# Main_Schematic.net
KiCad netlist of a schematic drawn in Altium Designer
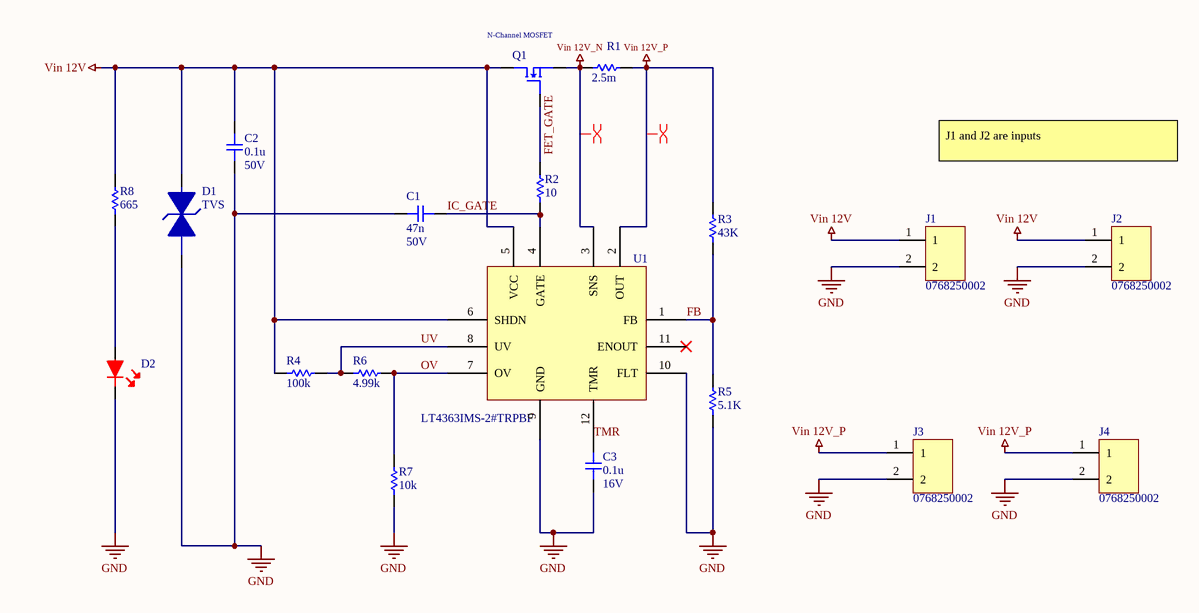
[diagram p0: Main Schematic.SchDoc]

(export (version "E")
  (design (tool "Eeschema 10.0.6"))
  (components
    (comp (ref "C1")
      (value "47n")
      (footprint "C0603")
      (description "C0603C 47nF Ceramic Multilayer Capacitor; 50 VDC; +125degC; X7R Dielec; +/-10%")
      (fields
        (field (name "MANUFACTURER") "KEMET")
        (field (name "MANUFACTURER PART NUMBER") "C0603C473K5RACTU")
        (field (name "VOLTAGE RATING (DC)") "50V")
      )
      (libsource (lib "Schlib1") (part "C0603C473K5RACTU"))
    )
    (comp (ref "C2")
      (value "0.1u")
      (footprint "C0805")
      (description "Cap Ceramic 0.1uF 50V Y5V -20% to 80% SMD 0805 85°C Paper T/R")
      (fields
        (field (name "MANUFACTURER") "KEMET")
        (field (name "MANUFACTURER PART NUMBER") "C0805C104Z5VACTU")
        (field (name "VOLTAGE RATING") "50V")
      )
      (libsource (lib "Schlib1") (part "C0805C104Z5VACTU"))
    )
    (comp (ref "C3")
      (value "0.1u")
      (footprint "C0603")
      (description "Cap Ceramic 0.1uF 16V X7R 20% SMD 0603 125°C Paper T/R")
      (fields
        (field (name "MANUFACTURER") "KEMET")
        (field (name "MANUFACTURER PART NUMBER") "C0603C104M4RACTU")
        (field (name "VOLTAGE RATING") "16V")
      )
      (libsource (lib "Schlib1") (part "C0603C104M4RACTU"))
    )
    (comp (ref "D1")
      (value "TVS")
      (footprint "TVS")
      (description "SMAJ Series 58 V 400 W SMT Uni-Directional TVS Diode - DO-214AC")
      (fields (field (name "MANUFACTURER") "Diodes") (field (name "MANUFACTURER PART NUMBER") "SMAJ58A-13-F"))
      (libsource (lib "Schlib1") (part "SMAJ58A-13-F"))
    )
    (comp (ref "D2")
      (value "R-LED")
      (footprint "D-0603")
      (description "LED Low-Power Uni-Color Red 630nm 2V 2-Pin Chip 0603(1608Metric) T/R")
      (fields
        (field (name "MANUFACTURER") "Wurth Electronics")
        (field (name "MANUFACTURER PART NUMBER") "150060RS75000")
      )
      (libsource (lib "Schlib1") (part "150060RS75000"))
    )
    (comp (ref "J1")
      (value "0768250002")
      (footprint "2X1PIN")
      (description "CONN HEADER R/A 2POS")
      (fields (field (name "MANUFACTURER") "Molex") (field (name "MANUFACTURER PART NUMBER") "76825-0002"))
      (libsource (lib "PDB_sch_lib") (part "2X1PIN"))
    )
    (comp (ref "J2")
      (value "0768250002")
      (footprint "2X1PIN")
      (description "CONN HEADER R/A 2POS")
      (fields (field (name "MANUFACTURER") "Molex") (field (name "MANUFACTURER PART NUMBER") "76825-0002"))
      (libsource (lib "PDB_sch_lib") (part "2X1PIN"))
    )
    (comp (ref "J3")
      (value "0768250002")
      (footprint "2X1PIN")
      (description "CONN HEADER R/A 2POS")
      (fields (field (name "MANUFACTURER") "Molex") (field (name "MANUFACTURER PART NUMBER") "76825-0002"))
      (libsource (lib "PDB_sch_lib") (part "2X1PIN"))
    )
    (comp (ref "J4")
      (value "0768250002")
      (footprint "2X1PIN")
      (description "CONN HEADER R/A 2POS")
      (fields (field (name "MANUFACTURER") "Molex") (field (name "MANUFACTURER PART NUMBER") "76825-0002"))
      (libsource (lib "PDB_sch_lib") (part "2X1PIN"))
    )
    (comp (ref "Q1")
      (value "N-Channel MOSFET")
      (footprint "N-MOS")
      (description "N-Channel Power MOSFET, UniFETTM, 250 V, 33 A, 94 mΩ, D2PAK")
      (fields
        (field (name "MANUFACTURER") "ON Semiconductor / Fairchild")
        (field (name "MANUFACTURER PART NUMBER") "FDB33N25TM")
      )
      (libsource (lib "Schlib1") (part "FDB33N25TM"))
    )
    (comp (ref "R1")
      (value "2.5m")
      (footprint "R3921")
      (description "Res Metal Strip 3921 0.0025 Ohm 1% 5W 50ppm/°C Pad SMD Automotive T/R")
      (fields
        (field (name "MANUFACTURER") "Vishay Dale")
        (field (name "MANUFACTURER PART NUMBER") "WSLP39212L500FEA")
      )
      (libsource (lib "Schlib1") (part "WSLP39212L500FEA"))
    )
    (comp (ref "R2")
      (value "10")
      (footprint "R0603")
      (description "KTR Series 0603 10 Ohm ±1 % 0.1 W ±100 ppm/°C Surface Mount Thick Film Resistor")
      (fields (field (name "MANUFACTURER") "Rohm") (field (name "MANUFACTURER PART NUMBER") "KTR03EZPF10R0"))
      (libsource (lib "Schlib1") (part "KTR03EZPF10R0"))
    )
    (comp (ref "R3")
      (value "43K")
      (footprint "R0603")
      (description "RNCF Precision Thin Film Chip Resistor 0603 Size 43K Ohm 0.5% 0.166 W 25 ppm/°C 2-Pin SMD T/R")
      (fields
        (field (name "MANUFACTURER") "Stackpole Electronics")
        (field (name "MANUFACTURER PART NUMBER") "RNCF0603DTE43K0")
      )
      (libsource (lib "Schlib1") (part "RNCF0603DTE43K0"))
    )
    (comp (ref "R4")
      (value "100k")
      (footprint "R0603")
      (description "Res Thick Film 0603 100K Ohm 1% 1/10W ±50ppm/°C Molded SMD Paper T/R")
      (fields
        (field (name "MANUFACTURER") "Yageo")
        (field (name "MANUFACTURER PART NUMBER") "RE0603FRE07100KL")
      )
      (libsource (lib "Schlib1") (part "RE0603FRE07100KL"))
    )
    (comp (ref "R5")
      (value "5.1K")
      (footprint "R0603")
      (description "Res Thick Film 0603 5.1K Ohm 1% 1/10W ±100ppm/°C Molded SMD Punched Carrier T/R")
      (fields
        (field (name "MANUFACTURER") "Panasonic")
        (field (name "MANUFACTURER PART NUMBER") "ERJ-3EKF5101V")
      )
      (libsource (lib "Schlib1") (part "ERJ-3EKF5101V"))
    )
    (comp (ref "R6")
      (value "4.99k")
      (footprint "R0603")
      (description "Res Thick Film 0603 4.99K Ohm 1% 1/10W ±100ppm/°C Molded SMD SMD Paper T/R")
      (fields
        (field (name "MANUFACTURER") "Stackpole Electronics")
        (field (name "MANUFACTURER PART NUMBER") "RMCF0603FT4K99")
      )
      (libsource (lib "Schlib1") (part "RMCF0603FT4K99"))
    )
    (comp (ref "R7")
      (value "10k")
      (footprint "R0603")
      (description "Res Thick Film 0603 10K Ohm 1% 1/10W ±100ppm/°C Molded SMD SMD T/R")
      (fields
        (field (name "MANUFACTURER") "Samsung")
        (field (name "MANUFACTURER PART NUMBER") "RC1608F103CS")
      )
      (libsource (lib "Schlib1") (part "RC1608F103CS"))
    )
    (comp (ref "R8")
      (value "665")
      (footprint "R0603")
      (description "Res Thick Film 0603 665 Ohm 1% 1/10W ±100ppm/°C Molded SMD Paper T/R")
      (fields
        (field (name "MANUFACTURER") "Yageo")
        (field (name "MANUFACTURER PART NUMBER") "RC0603FR-07665RL")
      )
      (libsource (lib "Schlib1") (part "RC0603FR-07665RL"))
    )
    (comp (ref "U1")
      (value "LT4363IMS-2#TRPBF")
      (footprint "TSOP65P490X110-12N")
      (description "Ms-Hot Swap/High Voltage High Voltage Surge Stopper With Current Limit. Auto-Retry After Fault")
      (fields (field (name "MANUFACTURER") "Analog Devices / Linear Technology"))
      (libsource (lib "Schlib1") (part "LT4363IMS-2#TRPBF"))
    )
  )
  (nets
    (net (code "1") (name "/FB") (class "Default")
      (node (ref "R3") (pin "1") (pinfunction "1_1") (pintype "passive"))
      (node (ref "R5") (pin "2") (pinfunction "2_2") (pintype "passive"))
      (node (ref "U1") (pin "1") (pinfunction "FB_1") (pintype "passive"))
    )
    (net (code "3") (name "/IC_GATE") (class "Default")
      (node (ref "C1") (pin "2") (pinfunction "2_2") (pintype "passive"))
      (node (ref "R2") (pin "1") (pinfunction "1_1") (pintype "passive"))
      (node (ref "U1") (pin "4") (pinfunction "GATE_4") (pintype "passive"))
    )
    (net (code "4") (name "/OV") (class "Default")
      (node (ref "R6") (pin "2") (pinfunction "2_2") (pintype "passive"))
      (node (ref "R7") (pin "2") (pinfunction "2_2") (pintype "passive"))
      (node (ref "U1") (pin "7") (pinfunction "OV_7") (pintype "passive"))
    )
    (net (code "5") (name "/TMR") (class "Default")
      (node (ref "C3") (pin "2") (pinfunction "2_2") (pintype "passive"))
      (node (ref "U1") (pin "12") (pinfunction "TMR_12") (pintype "passive"))
    )
    (net (code "6") (name "/UV") (class "Default")
      (node (ref "R4") (pin "2") (pinfunction "2_2") (pintype "passive"))
      (node (ref "R6") (pin "1") (pinfunction "1_1") (pintype "passive"))
      (node (ref "U1") (pin "8") (pinfunction "UV_8") (pintype "passive"))
    )
    (net (code "7") (name "GND") (class "Default")
      (node (ref "C1") (pin "1") (pinfunction "1_1") (pintype "passive"))
      (node (ref "C2") (pin "1") (pinfunction "1_1") (pintype "passive"))
      (node (ref "C3") (pin "1") (pinfunction "1_1") (pintype "passive"))
      (node (ref "D1") (pin "2") (pinfunction "2_2") (pintype "passive"))
      (node (ref "D2") (pin "2") (pinfunction "2_2") (pintype "passive"))
      (node (ref "J1") (pin "2") (pinfunction "2_2") (pintype "passive"))
      (node (ref "J2") (pin "2") (pinfunction "2_2") (pintype "passive"))
      (node (ref "J3") (pin "2") (pinfunction "2_2") (pintype "passive"))
      (node (ref "J4") (pin "2") (pinfunction "2_2") (pintype "passive"))
      (node (ref "R5") (pin "1") (pinfunction "1_1") (pintype "passive"))
      (node (ref "R7") (pin "1") (pinfunction "1_1") (pintype "passive"))
      (node (ref "U1") (pin "10") (pinfunction "FLT_10") (pintype "passive"))
      (node (ref "U1") (pin "9") (pinfunction "GND_9") (pintype "passive"))
    )
    (net (code "8") (name "Net-(D2-Pad1)") (class "Default")
      (node (ref "D2") (pin "1") (pinfunction "1_1") (pintype "passive"))
      (node (ref "R8") (pin "1") (pinfunction "1_1") (pintype "passive"))
    )
    (net (code "9") (name "Net-(Q1-Pad1)") (class "Default")
      (node (ref "Q1") (pin "1") (pinfunction "1_1") (pintype "passive"))
      (node (ref "R2") (pin "2") (pinfunction "2_2") (pintype "passive"))
    )
    (net (code "10") (name "Vin 12V") (class "Default")
      (node (ref "C2") (pin "2") (pinfunction "2_2") (pintype "passive"))
      (node (ref "D1") (pin "1") (pinfunction "1_1") (pintype "passive"))
      (node (ref "J1") (pin "1") (pinfunction "1_1") (pintype "passive"))
      (node (ref "J2") (pin "1") (pinfunction "1_1") (pintype "passive"))
      (node (ref "Q1") (pin "2") (pinfunction "2_2") (pintype "passive"))
      (node (ref "R4") (pin "1") (pinfunction "1_1") (pintype "passive"))
      (node (ref "R8") (pin "2") (pinfunction "2_2") (pintype "passive"))
      (node (ref "U1") (pin "5") (pinfunction "VCC_5") (pintype "passive"))
      (node (ref "U1") (pin "6") (pinfunction "SHDN_6") (pintype "passive"))
    )
    (net (code "11") (name "Vin 12V_N") (class "Default")
      (node (ref "Q1") (pin "3") (pinfunction "3_3") (pintype "passive"))
      (node (ref "R1") (pin "1") (pinfunction "1_1") (pintype "passive"))
      (node (ref "U1") (pin "3") (pinfunction "SNS_3") (pintype "passive"))
    )
    (net (code "12") (name "Vin 12V_P") (class "Default")
      (node (ref "J3") (pin "1") (pinfunction "1_1") (pintype "passive"))
      (node (ref "J4") (pin "1") (pinfunction "1_1") (pintype "passive"))
      (node (ref "R1") (pin "2") (pinfunction "2_2") (pintype "passive"))
      (node (ref "R3") (pin "2") (pinfunction "2_2") (pintype "passive"))
      (node (ref "U1") (pin "2") (pinfunction "OUT_2") (pintype "passive"))
    )
    (net (code "13") (name "unconnected-(U1-ENOUT-Pad11)") (class "Default")
      (node (ref "U1") (pin "11") (pinfunction "ENOUT_11") (pintype "passive+no_connect"))
    )
  )
)
